# riffleBoost-REVA.net
KiCad netlist of a schematic drawn in EAGLE
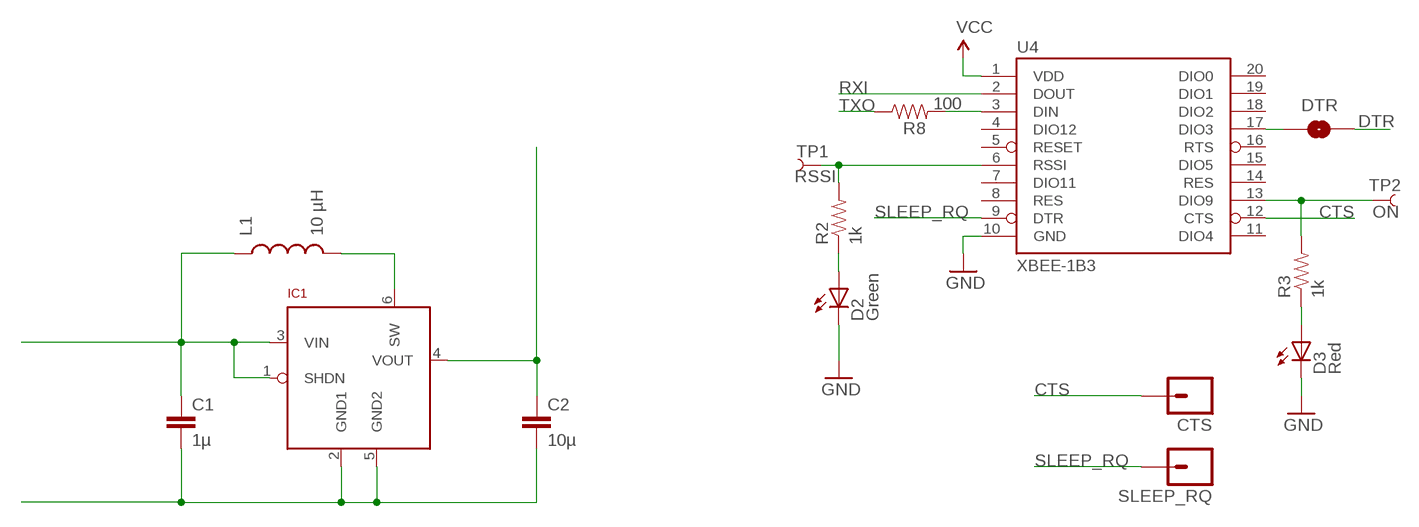
[diagram p0: schematic, sheet 1]

(export (version "E")
  (design (tool "Eeschema 10.0.6"))
  (components
    (comp (ref "C1")
      (value "1µ")
      (footprint "eagle-import:0603-CAP")
      (libsource (lib "eagle-import") (part "CAP0603-CAP"))
    )
    (comp (ref "C2")
      (value "10µ")
      (footprint "eagle-import:0805")
      (libsource (lib "eagle-import") (part "CAP0805"))
    )
    (comp (ref "CTS")
      (value "M01PTH")
      (footprint "eagle-import:1X01")
      (libsource (lib "eagle-import") (part "M01PTH"))
    )
    (comp (ref "D2")
      (value "Green")
      (footprint "eagle-import:LED-0603")
      (libsource (lib "eagle-import") (part "LED0603"))
    )
    (comp (ref "D3")
      (value "Red")
      (footprint "eagle-import:LED-0603")
      (libsource (lib "eagle-import") (part "LED0603"))
    )
    (comp (ref "DTR")
      (value "SOLDERJUMPERNC")
      (footprint "eagle-import:SJ_2S")
      (libsource (lib "eagle-import") (part "SOLDERJUMPERNC"))
    )
    (comp (ref "IC1")
      (value "LTC3525")
      (footprint "eagle-import:SC70")
      (libsource (lib "eagle-import") (part "LTC3525"))
    )
    (comp (ref "L1")
      (value "10 µH")
      (footprint "eagle-import:1210")
      (libsource (lib "eagle-import") (part "INDUCTOR1210"))
    )
    (comp (ref "R2")
      (value "1k")
      (footprint "eagle-import:0402-RES")
      (libsource (lib "eagle-import") (part "RESISTOR0402-RES"))
    )
    (comp (ref "R3")
      (value "1k")
      (footprint "eagle-import:0402-RES")
      (libsource (lib "eagle-import") (part "RESISTOR0402-RES"))
    )
    (comp (ref "R8")
      (value "100")
      (footprint "eagle-import:0402-RES")
      (libsource (lib "eagle-import") (part "RESISTOR0402-RES"))
    )
    (comp (ref "SLEEP_RQ")
      (value "M01PTH")
      (footprint "eagle-import:1X01")
      (libsource (lib "eagle-import") (part "M01PTH"))
    )
    (comp (ref "TP1")
      (value "RSSI")
      (footprint "eagle-import:PAD.03X.05")
      (libsource (lib "eagle-import") (part "TEST-POINT3X5"))
    )
    (comp (ref "TP2")
      (value "ON")
      (footprint "eagle-import:PAD.03X.05")
      (libsource (lib "eagle-import") (part "TEST-POINT3X5"))
    )
    (comp (ref "U4")
      (value "XBEE-1B3")
      (footprint "eagle-import:XBEE-SMD")
      (libsource (lib "eagle-import") (part "XBEE-1B3"))
    )
  )
  (nets
    (net (code "1") (name "/CTS") (class "Default")
      (node (ref "CTS") (pin "1") (pinfunction "1_1") (pintype "passive"))
      (node (ref "U4") (pin "12") (pinfunction "CTS_12") (pintype "output"))
    )
    (net (code "2") (name "/DTR") (class "Default")
      (node (ref "DTR") (pin "2") (pinfunction "2_2") (pintype "passive"))
    )
    (net (code "3") (name "/RXI") (class "Default")
      (node (ref "U4") (pin "2") (pinfunction "DOUT_2") (pintype "output"))
    )
    (net (code "4") (name "/SLEEP_RQ") (class "Default")
      (node (ref "SLEEP_RQ") (pin "1") (pinfunction "1_1") (pintype "passive"))
      (node (ref "U4") (pin "9") (pinfunction "DTR_9") (pintype "bidirectional"))
    )
    (net (code "5") (name "/TXO") (class "Default")
      (node (ref "R8") (pin "1") (pinfunction "1_1") (pintype "passive"))
    )
    (net (code "6") (name "GND") (class "Default")
      (node (ref "C1") (pin "2") (pinfunction "2_2") (pintype "passive"))
      (node (ref "C2") (pin "2") (pinfunction "2_2") (pintype "passive"))
      (node (ref "D2") (pin "C") (pinfunction "C_C") (pintype "passive"))
      (node (ref "D3") (pin "C") (pinfunction "C_C") (pintype "passive"))
      (node (ref "IC1") (pin "2") (pinfunction "GND1_2") (pintype "power_in"))
      (node (ref "IC1") (pin "5") (pinfunction "GND2_5") (pintype "power_in"))
      (node (ref "U4") (pin "10") (pinfunction "GND_10") (pintype "power_in"))
    )
    (net (code "7") (name "Net-(D2-PadA)") (class "Default")
      (node (ref "D2") (pin "A") (pinfunction "A_A") (pintype "passive"))
      (node (ref "R2") (pin "1") (pinfunction "1_1") (pintype "passive"))
    )
    (net (code "8") (name "Net-(D3-PadA)") (class "Default")
      (node (ref "D3") (pin "A") (pinfunction "A_A") (pintype "passive"))
      (node (ref "R3") (pin "1") (pinfunction "1_1") (pintype "passive"))
    )
    (net (code "9") (name "Net-(IC1-SHDN)") (class "Default")
      (node (ref "C1") (pin "1") (pinfunction "1_1") (pintype "passive"))
      (node (ref "IC1") (pin "1") (pinfunction "SHDN_1") (pintype "input"))
      (node (ref "IC1") (pin "3") (pinfunction "VIN_3") (pintype "tri_state"))
      (node (ref "L1") (pin "1") (pinfunction "1_1") (pintype "passive"))
    )
    (net (code "10") (name "Net-(IC1-SW)") (class "Default")
      (node (ref "IC1") (pin "6") (pinfunction "SW_6") (pintype "power_in"))
      (node (ref "L1") (pin "2") (pinfunction "2_2") (pintype "passive"))
    )
    (net (code "11") (name "Net-(TP1-1)") (class "Default")
      (node (ref "R2") (pin "2") (pinfunction "2_2") (pintype "passive"))
      (node (ref "TP1") (pin "P$1") (pinfunction "1_P$1") (pintype "bidirectional"))
      (node (ref "U4") (pin "6") (pinfunction "RSSI_6") (pintype "bidirectional"))
    )
    (net (code "12") (name "Net-(TP2-1)") (class "Default")
      (node (ref "R3") (pin "2") (pinfunction "2_2") (pintype "passive"))
      (node (ref "TP2") (pin "P$1") (pinfunction "1_P$1") (pintype "bidirectional"))
      (node (ref "U4") (pin "13") (pinfunction "DIO9_13") (pintype "bidirectional"))
    )
    (net (code "13") (name "Net-(U4-DIN)") (class "Default")
      (node (ref "R8") (pin "2") (pinfunction "2_2") (pintype "passive"))
      (node (ref "U4") (pin "3") (pinfunction "DIN_3") (pintype "input"))
    )
    (net (code "14") (name "Net-(U4-DIO3)") (class "Default")
      (node (ref "DTR") (pin "1") (pinfunction "1_1") (pintype "passive"))
      (node (ref "U4") (pin "17") (pinfunction "DIO3_17") (pintype "bidirectional"))
    )
    (net (code "15") (name "VCC") (class "Default")
      (node (ref "C2") (pin "1") (pinfunction "1_1") (pintype "passive"))
      (node (ref "IC1") (pin "4") (pinfunction "VOUT_4") (pintype "power_in"))
      (node (ref "U4") (pin "1") (pinfunction "VDD_1") (pintype "power_in"))
    )
    (net (code "16") (name "unconnected-(U4-DIO0-Pad20)") (class "Default")
      (node (ref "U4") (pin "20") (pinfunction "DIO0_20") (pintype "bidirectional"))
    )
    (net (code "17") (name "unconnected-(U4-DIO1-Pad19)") (class "Default")
      (node (ref "U4") (pin "19") (pinfunction "DIO1_19") (pintype "bidirectional"))
    )
    (net (code "18") (name "unconnected-(U4-DIO2-Pad18)") (class "Default")
      (node (ref "U4") (pin "18") (pinfunction "DIO2_18") (pintype "bidirectional"))
    )
    (net (code "19") (name "unconnected-(U4-DIO4-Pad11)") (class "Default")
      (node (ref "U4") (pin "11") (pinfunction "DIO4_11") (pintype "bidirectional"))
    )
    (net (code "20") (name "unconnected-(U4-DIO5-Pad15)") (class "Default")
      (node (ref "U4") (pin "15") (pinfunction "DIO5_15") (pintype "bidirectional"))
    )
    (net (code "21") (name "unconnected-(U4-DIO11-Pad7)") (class "Default")
      (node (ref "U4") (pin "7") (pinfunction "DIO11_7") (pintype "bidirectional"))
    )
    (net (code "22") (name "unconnected-(U4-DIO12-Pad4)") (class "Default")
      (node (ref "U4") (pin "4") (pinfunction "DIO12_4") (pintype "bidirectional"))
    )
    (net (code "23") (name "unconnected-(U4-RES-Pad8)") (class "Default")
      (node (ref "U4") (pin "8") (pinfunction "RES_8") (pintype "bidirectional"))
    )
    (net (code "24") (name "unconnected-(U4-RES-Pad14)") (class "Default")
      (node (ref "U4") (pin "14") (pinfunction "RES_14") (pintype "bidirectional"))
    )
    (net (code "25") (name "unconnected-(U4-RESET-Pad5)") (class "Default")
      (node (ref "U4") (pin "5") (pinfunction "RESET_5") (pintype "input"))
    )
    (net (code "26") (name "unconnected-(U4-RTS-Pad16)") (class "Default")
      (node (ref "U4") (pin "16") (pinfunction "RTS_16") (pintype "input"))
    )
  )
)
